# MIDI_board.net
KiCad netlist of a schematic drawn in EAGLE
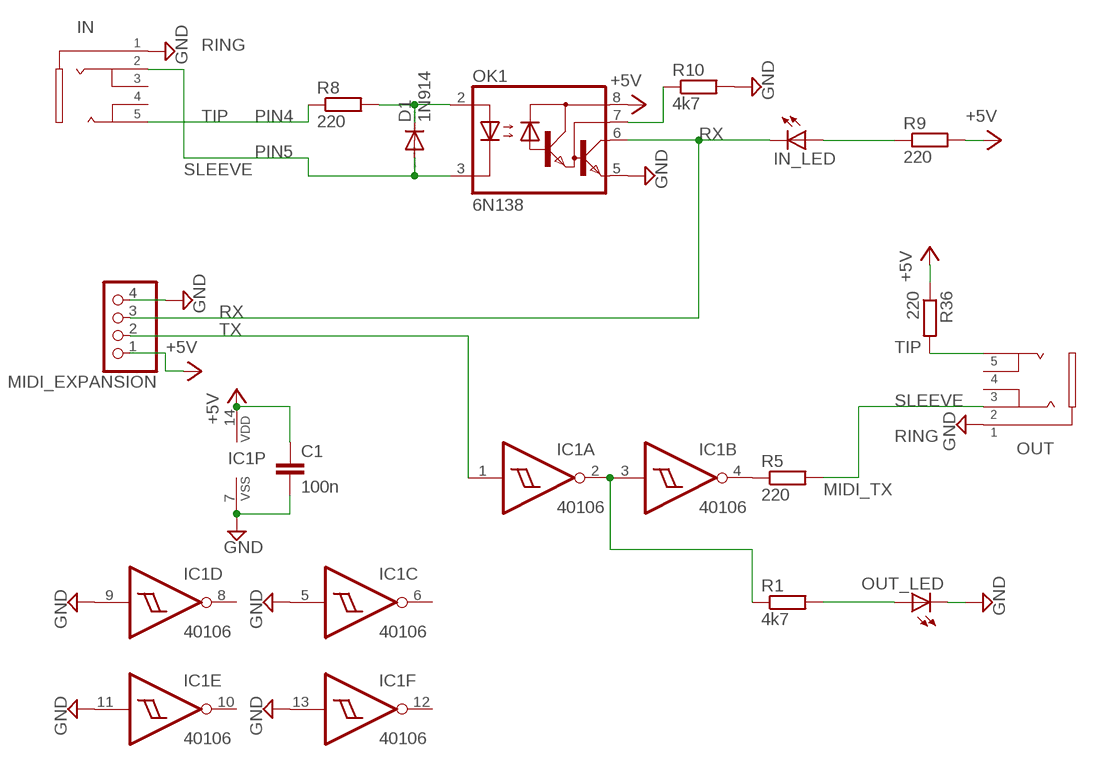
[diagram p0: schematic, sheet 1]

(export (version "E")
  (design (tool "Eeschema 10.0.6"))
  (components
    (comp (ref "C1")
      (value "100n")
      (footprint "eagle-import:C050-025X075")
      (libsource (lib "eagle-import") (part "C-EU050-025X075"))
    )
    (comp (ref "D1")
      (value "1N914")
      (footprint "eagle-import:D-6.35")
      (libsource (lib "eagle-import") (part "1N914"))
    )
    (comp (ref "IC1")
      (value "40106")
      (footprint "eagle-import:DIL14")
      (libsource (lib "eagle-import") (part "40106N"))
    )
    (comp (ref "IN")
      (value "PJ-324MH")
      (footprint "eagle-import:PJ-324MH")
      (libsource (lib "eagle-import") (part "PJ-324MH"))
    )
    (comp (ref "IN_LED")
      (value "LED3MM-NB")
      (footprint "eagle-import:LED3MM")
      (libsource (lib "eagle-import") (part "LED3MM-NB"))
    )
    (comp (ref "MIDI_EXPANSION")
      (value "PINHD-1X4")
      (footprint "eagle-import:1X04")
      (libsource (lib "eagle-import") (part "PINHD-1X4"))
    )
    (comp (ref "OK1")
      (value "6N138")
      (footprint "eagle-import:DIL08")
      (fields (field (name "MF") "VISHAY/TELEFUNKEN"))
      (libsource (lib "eagle-import") (part "6N138"))
    )
    (comp (ref "OUT")
      (value "PJ-324MH")
      (footprint "eagle-import:PJ-324MH")
      (libsource (lib "eagle-import") (part "PJ-324MH"))
    )
    (comp (ref "OUT_LED")
      (value "LED3MM-NB")
      (footprint "eagle-import:LED3MM")
      (libsource (lib "eagle-import") (part "LED3MM-NB"))
    )
    (comp (ref "R1")
      (value "4k7")
      (footprint "eagle-import:0204_7")
      (libsource (lib "eagle-import") (part "BOX-RESISTOR"))
    )
    (comp (ref "R5")
      (value "220")
      (footprint "eagle-import:0204_7")
      (libsource (lib "eagle-import") (part "BOX-RESISTOR"))
    )
    (comp (ref "R8")
      (value "220")
      (footprint "eagle-import:0204_7")
      (libsource (lib "eagle-import") (part "BOX-RESISTOR"))
    )
    (comp (ref "R9")
      (value "220")
      (footprint "eagle-import:0204_7")
      (libsource (lib "eagle-import") (part "BOX-RESISTOR"))
    )
    (comp (ref "R10")
      (value "4k7")
      (footprint "eagle-import:0204_7")
      (libsource (lib "eagle-import") (part "BOX-RESISTOR"))
    )
    (comp (ref "R36")
      (value "220")
      (footprint "eagle-import:0204_7")
      (libsource (lib "eagle-import") (part "BOX-RESISTOR"))
    )
  )
  (nets
    (net (code "1") (name "+5V") (class "Default")
      (node (ref "C1") (pin "1") (pinfunction "1_1") (pintype "passive"))
      (node (ref "IC1") (pin "14") (pinfunction "VDD_14") (pintype "power_in"))
      (node (ref "MIDI_EXPANSION") (pin "1") (pinfunction "1_1") (pintype "passive"))
      (node (ref "OK1") (pin "8") (pinfunction "VCC_8") (pintype "passive"))
      (node (ref "R36") (pin "1") (pinfunction "1_1") (pintype "passive"))
      (node (ref "R9") (pin "2") (pinfunction "2_2") (pintype "passive"))
    )
    (net (code "2") (name "/MIDI_TX") (class "Default")
      (node (ref "OUT") (pin "2") (pinfunction "2_2") (pintype "passive"))
      (node (ref "R5") (pin "2") (pinfunction "2_2") (pintype "passive"))
    )
    (net (code "3") (name "/PIN4") (class "Default")
      (node (ref "IN") (pin "5") (pinfunction "5_5") (pintype "passive"))
      (node (ref "R8") (pin "1") (pinfunction "1_1") (pintype "passive"))
    )
    (net (code "4") (name "/PIN5") (class "Default")
      (node (ref "D1") (pin "A") (pinfunction "A_A") (pintype "passive"))
      (node (ref "IN") (pin "2") (pinfunction "2_2") (pintype "passive"))
      (node (ref "OK1") (pin "3") (pinfunction "C_3") (pintype "passive"))
    )
    (net (code "5") (name "/RX") (class "Default")
      (node (ref "IN_LED") (pin "K") (pinfunction "C_K") (pintype "passive"))
      (node (ref "MIDI_EXPANSION") (pin "3") (pinfunction "3_3") (pintype "passive"))
      (node (ref "OK1") (pin "6") (pinfunction "VO_6") (pintype "passive"))
    )
    (net (code "6") (name "/TX") (class "Default")
      (node (ref "IC1") (pin "1") (pinfunction "I_1") (pintype "input"))
      (node (ref "MIDI_EXPANSION") (pin "2") (pinfunction "2_2") (pintype "passive"))
    )
    (net (code "7") (name "GND") (class "Default")
      (node (ref "C1") (pin "2") (pinfunction "2_2") (pintype "passive"))
      (node (ref "IC1") (pin "11") (pinfunction "I_11") (pintype "input"))
      (node (ref "IC1") (pin "13") (pinfunction "I_13") (pintype "input"))
      (node (ref "IC1") (pin "5") (pinfunction "I_5") (pintype "input"))
      (node (ref "IC1") (pin "7") (pinfunction "VSS_7") (pintype "power_in"))
      (node (ref "IC1") (pin "9") (pinfunction "I_9") (pintype "input"))
      (node (ref "IN") (pin "1") (pinfunction "1_1") (pintype "passive"))
      (node (ref "MIDI_EXPANSION") (pin "4") (pinfunction "4_4") (pintype "passive"))
      (node (ref "OK1") (pin "5") (pinfunction "GND_5") (pintype "passive"))
      (node (ref "OUT") (pin "1") (pinfunction "1_1") (pintype "passive"))
      (node (ref "OUT_LED") (pin "K") (pinfunction "C_K") (pintype "passive"))
      (node (ref "R10") (pin "2") (pinfunction "2_2") (pintype "passive"))
    )
    (net (code "8") (name "Net-(IC1A-O)") (class "Default")
      (node (ref "IC1") (pin "2") (pinfunction "O_2") (pintype "output"))
      (node (ref "IC1") (pin "3") (pinfunction "I_3") (pintype "input"))
      (node (ref "R1") (pin "1") (pinfunction "1_1") (pintype "passive"))
    )
    (net (code "9") (name "Net-(IC1B-O)") (class "Default")
      (node (ref "IC1") (pin "4") (pinfunction "O_4") (pintype "output"))
      (node (ref "R5") (pin "1") (pinfunction "1_1") (pintype "passive"))
    )
    (net (code "10") (name "Net-(IN_LED-PadA)") (class "Default")
      (node (ref "IN_LED") (pin "A") (pinfunction "A_A") (pintype "passive"))
      (node (ref "R9") (pin "1") (pinfunction "1_1") (pintype "passive"))
    )
    (net (code "11") (name "Net-(OK1-A)") (class "Default")
      (node (ref "D1") (pin "C") (pinfunction "C_C") (pintype "passive"))
      (node (ref "OK1") (pin "2") (pinfunction "A_2") (pintype "passive"))
      (node (ref "R8") (pin "2") (pinfunction "2_2") (pintype "passive"))
    )
    (net (code "12") (name "Net-(OK1-VB)") (class "Default")
      (node (ref "OK1") (pin "7") (pinfunction "VB_7") (pintype "passive"))
      (node (ref "R10") (pin "1") (pinfunction "1_1") (pintype "passive"))
    )
    (net (code "13") (name "Net-(OUT-Pad5)") (class "Default")
      (node (ref "OUT") (pin "5") (pinfunction "5_5") (pintype "passive"))
      (node (ref "R36") (pin "2") (pinfunction "2_2") (pintype "passive"))
    )
    (net (code "14") (name "Net-(OUT_LED-PadA)") (class "Default")
      (node (ref "OUT_LED") (pin "A") (pinfunction "A_A") (pintype "passive"))
      (node (ref "R1") (pin "2") (pinfunction "2_2") (pintype "passive"))
    )
    (net (code "15") (name "unconnected-(IC1C-O-Pad6)") (class "Default")
      (node (ref "IC1") (pin "6") (pinfunction "O_6") (pintype "output"))
    )
    (net (code "16") (name "unconnected-(IC1D-O-Pad8)") (class "Default")
      (node (ref "IC1") (pin "8") (pinfunction "O_8") (pintype "output"))
    )
    (net (code "17") (name "unconnected-(IC1E-O-Pad10)") (class "Default")
      (node (ref "IC1") (pin "10") (pinfunction "O_10") (pintype "output"))
    )
    (net (code "18") (name "unconnected-(IC1F-O-Pad12)") (class "Default")
      (node (ref "IC1") (pin "12") (pinfunction "O_12") (pintype "output"))
    )
    (net (code "19") (name "unconnected-(IN-Pad3)") (class "Default")
      (node (ref "IN") (pin "3") (pinfunction "3_3") (pintype "passive"))
    )
    (net (code "20") (name "unconnected-(IN-Pad4)") (class "Default")
      (node (ref "IN") (pin "4") (pinfunction "4_4") (pintype "passive"))
    )
    (net (code "21") (name "unconnected-(OUT-Pad3)") (class "Default")
      (node (ref "OUT") (pin "3") (pinfunction "3_3") (pintype "passive"))
    )
    (net (code "22") (name "unconnected-(OUT-Pad4)") (class "Default")
      (node (ref "OUT") (pin "4") (pinfunction "4_4") (pintype "passive"))
    )
  )
)
